# s3-pilot2.net
KiCad netlist of a schematic drawn in EAGLE
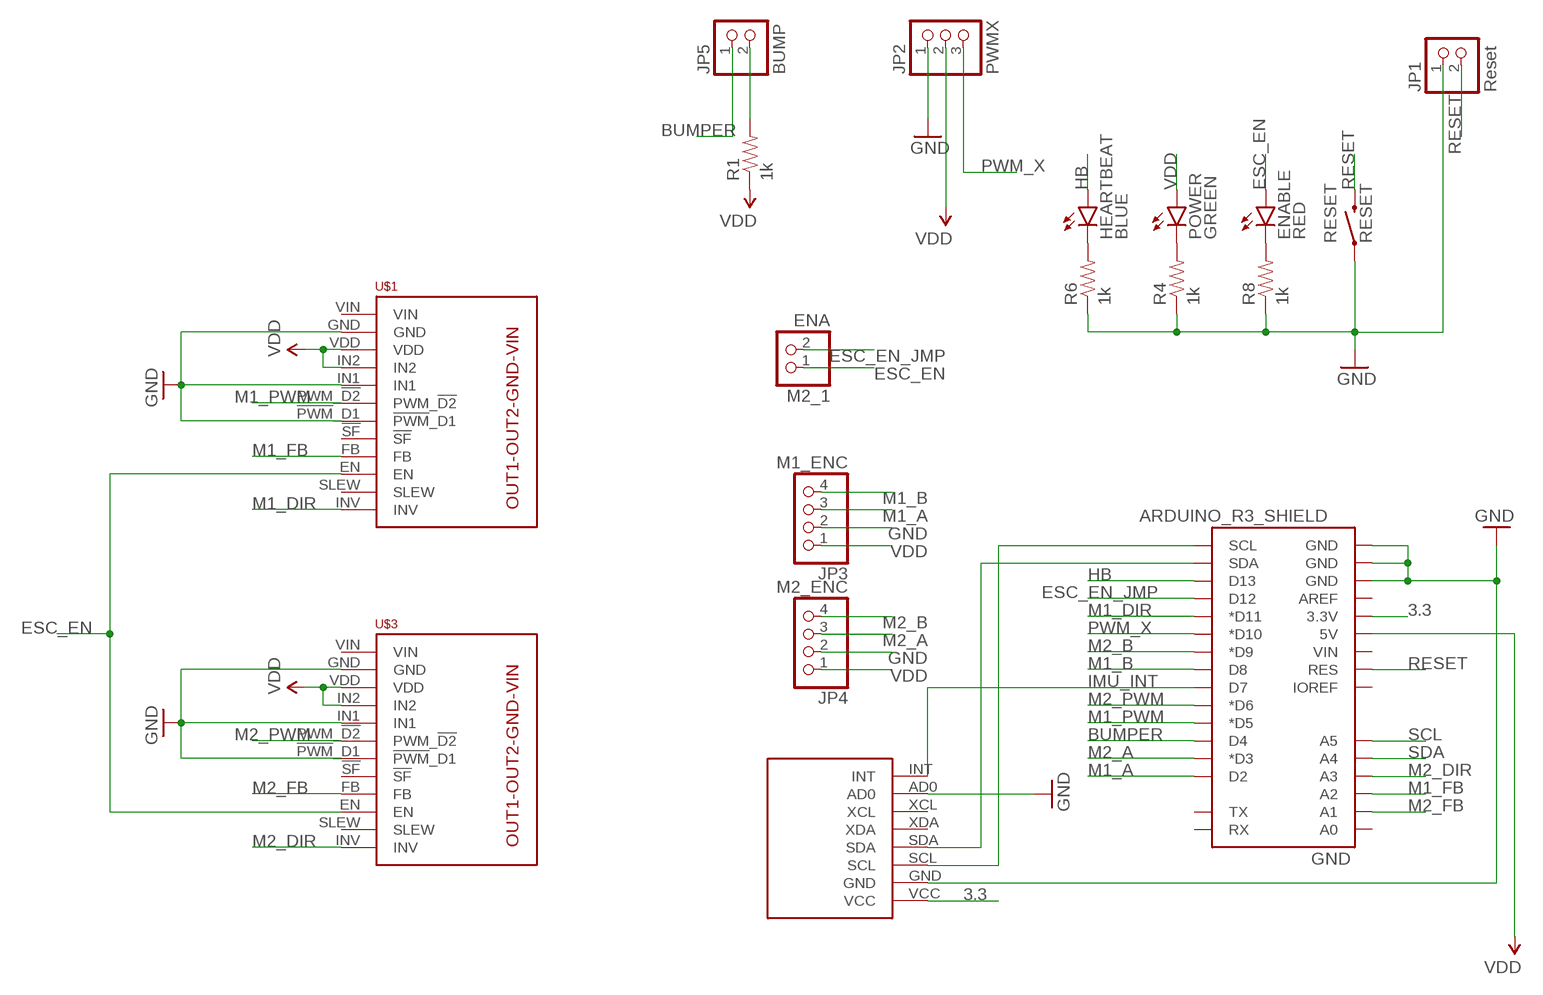
[diagram p0: schematic, sheet 1]

(export (version "E")
  (design (tool "Eeschema 10.0.6"))
  (components
    (comp (ref "ENABLE")
      (value "RED")
      (footprint "eagle-import:LED-1206")
      (libsource (lib "eagle-import") (part "LED-RED1206"))
    )
    (comp (ref "GND")
      (value "ARDUINO_R3_SHIELD")
      (footprint "eagle-import:UNO_R3_SHIELD")
      (libsource (lib "eagle-import") (part "ARDUINO_R3_SHIELD"))
    )
    (comp (ref "HEARTBEAT")
      (value "BLUE")
      (footprint "eagle-import:LED-1206")
      (libsource (lib "eagle-import") (part "LED-BLUE1206"))
    )
    (comp (ref "JP1")
      (value "Reset")
      (footprint "eagle-import:1X02")
      (libsource (lib "eagle-import") (part "PINHD-1X2"))
    )
    (comp (ref "JP2")
      (value "PWMX")
      (footprint "eagle-import:1X03_90")
      (libsource (lib "eagle-import") (part "PINHD-1X3/90"))
    )
    (comp (ref "JP3")
      (value "M1_ENC")
      (footprint "eagle-import:1X04_90")
      (libsource (lib "eagle-import") (part "PINHD-1X4/90"))
    )
    (comp (ref "JP4")
      (value "M2_ENC")
      (footprint "eagle-import:1X04_90")
      (libsource (lib "eagle-import") (part "PINHD-1X4/90"))
    )
    (comp (ref "JP5")
      (value "BUMP")
      (footprint "eagle-import:1X02_90")
      (libsource (lib "eagle-import") (part "PINHD-1X2/90"))
    )
    (comp (ref "M2_1")
      (value "ENA")
      (footprint "eagle-import:1X02")
      (libsource (lib "eagle-import") (part "PINHD-1X2"))
    )
    (comp (ref "MPU6050")
      (value "MPU-6050-BO")
      (footprint "eagle-import:MPU-6050-BO")
      (libsource (lib "eagle-import") (part "MPU-6050-BO"))
    )
    (comp (ref "POWER")
      (value "GREEN")
      (footprint "eagle-import:LED-1206")
      (libsource (lib "eagle-import") (part "LED-GREENLARGE"))
    )
    (comp (ref "R1")
      (value "1k")
      (footprint "eagle-import:1206")
      (libsource (lib "eagle-import") (part "RESISTOR1206"))
    )
    (comp (ref "R4")
      (value "1k")
      (footprint "eagle-import:1206")
      (libsource (lib "eagle-import") (part "RESISTOR1206"))
    )
    (comp (ref "R6")
      (value "1k")
      (footprint "eagle-import:1206")
      (libsource (lib "eagle-import") (part "RESISTOR1206"))
    )
    (comp (ref "R8")
      (value "1k")
      (footprint "eagle-import:1206")
      (libsource (lib "eagle-import") (part "RESISTOR1206"))
    )
    (comp (ref "RESET")
      (value "RESET")
      (footprint "eagle-import:TACTILE_SWITCH_TALL")
      (libsource (lib "eagle-import") (part "SWITCH-MOMENTARY-2SMD-4"))
    )
    (comp (ref "U$1")
      (value "M1")
      (footprint "eagle-import:MC33926-SINGLE-BO")
      (libsource (lib "eagle-import") (part "MC33926-SINGLE-BO"))
    )
    (comp (ref "U$3")
      (value "M2")
      (footprint "eagle-import:MC33926-SINGLE-BO")
      (libsource (lib "eagle-import") (part "MC33926-SINGLE-BO"))
    )
  )
  (nets
    (net (code "1") (name "/3.3") (class "Default")
      (node (ref "GND") (pin "3.3V") (pinfunction "3.3V_3.3V") (pintype "bidirectional"))
      (node (ref "MPU6050") (pin "VCC") (pinfunction "VCC_VCC") (pintype "power_in"))
    )
    (net (code "2") (name "/BUMPER") (class "Default")
      (node (ref "GND") (pin "D4") (pinfunction "D4_D4") (pintype "bidirectional"))
      (node (ref "JP5") (pin "1") (pinfunction "1_1") (pintype "passive"))
    )
    (net (code "3") (name "/ESC_EN") (class "Default")
      (node (ref "ENABLE") (pin "A") (pinfunction "A_A") (pintype "passive"))
      (node (ref "M2_1") (pin "1") (pinfunction "1_1") (pintype "passive"))
      (node (ref "U$1") (pin "EN") (pinfunction "EN_EN") (pintype "input"))
      (node (ref "U$3") (pin "EN") (pinfunction "EN_EN") (pintype "input"))
    )
    (net (code "4") (name "/ESC_EN_JMP") (class "Default")
      (node (ref "GND") (pin "D12") (pinfunction "D12_D12") (pintype "bidirectional"))
      (node (ref "M2_1") (pin "2") (pinfunction "2_2") (pintype "passive"))
    )
    (net (code "5") (name "/HB") (class "Default")
      (node (ref "GND") (pin "D13") (pinfunction "D13_D13") (pintype "bidirectional"))
      (node (ref "HEARTBEAT") (pin "A") (pinfunction "A_A") (pintype "passive"))
    )
    (net (code "6") (name "/IMU_INT") (class "Default")
      (node (ref "GND") (pin "D7") (pinfunction "D7_D7") (pintype "bidirectional"))
      (node (ref "MPU6050") (pin "INT") (pinfunction "INT_INT") (pintype "output"))
    )
    (net (code "7") (name "/M1_A") (class "Default")
      (node (ref "GND") (pin "D2") (pinfunction "D2_D2") (pintype "bidirectional"))
      (node (ref "JP3") (pin "3") (pinfunction "3_3") (pintype "passive"))
    )
    (net (code "8") (name "/M1_B") (class "Default")
      (node (ref "GND") (pin "D8") (pinfunction "D8_D8") (pintype "bidirectional"))
      (node (ref "JP3") (pin "4") (pinfunction "4_4") (pintype "passive"))
    )
    (net (code "9") (name "/M1_DIR") (class "Default")
      (node (ref "GND") (pin "D11") (pinfunction "*D11_D11") (pintype "bidirectional"))
      (node (ref "U$1") (pin "INV") (pinfunction "INV_INV") (pintype "input"))
    )
    (net (code "10") (name "/M1_FB") (class "Default")
      (node (ref "GND") (pin "A2") (pinfunction "A2_A2") (pintype "bidirectional"))
      (node (ref "U$1") (pin "FB") (pinfunction "FB_FB") (pintype "output"))
    )
    (net (code "11") (name "/M1_PWM") (class "Default")
      (node (ref "GND") (pin "D5") (pinfunction "*D5_D5") (pintype "bidirectional"))
      (node (ref "U$1") (pin "PWM_!D2") (pinfunction "PWM_~{D2}_PWM_!D2") (pintype "input"))
    )
    (net (code "12") (name "/M2_A") (class "Default")
      (node (ref "GND") (pin "D3") (pinfunction "*D3_D3") (pintype "bidirectional"))
      (node (ref "JP4") (pin "3") (pinfunction "3_3") (pintype "passive"))
    )
    (net (code "13") (name "/M2_B") (class "Default")
      (node (ref "GND") (pin "D9") (pinfunction "*D9_D9") (pintype "bidirectional"))
      (node (ref "JP4") (pin "4") (pinfunction "4_4") (pintype "passive"))
    )
    (net (code "14") (name "/M2_DIR") (class "Default")
      (node (ref "GND") (pin "A3") (pinfunction "A3_A3") (pintype "bidirectional"))
      (node (ref "U$3") (pin "INV") (pinfunction "INV_INV") (pintype "input"))
    )
    (net (code "15") (name "/M2_FB") (class "Default")
      (node (ref "GND") (pin "A1") (pinfunction "A1_A1") (pintype "bidirectional"))
      (node (ref "U$3") (pin "FB") (pinfunction "FB_FB") (pintype "output"))
    )
    (net (code "16") (name "/M2_PWM") (class "Default")
      (node (ref "GND") (pin "D6") (pinfunction "*D6_D6") (pintype "bidirectional"))
      (node (ref "U$3") (pin "PWM_!D2") (pinfunction "PWM_~{D2}_PWM_!D2") (pintype "input"))
    )
    (net (code "17") (name "/PWM_X") (class "Default")
      (node (ref "GND") (pin "D10") (pinfunction "*D10_D10") (pintype "bidirectional"))
      (node (ref "JP2") (pin "3") (pinfunction "3_3") (pintype "passive"))
    )
    (net (code "18") (name "/RESET") (class "Default")
      (node (ref "GND") (pin "RES") (pinfunction "RES_RES") (pintype "bidirectional"))
      (node (ref "JP1") (pin "2") (pinfunction "2_2") (pintype "passive"))
      (node (ref "RESET") (pin "B2") (pinfunction "2_B2") (pintype "passive"))
    )
    (net (code "19") (name "/SCL") (class "Default")
      (node (ref "GND") (pin "A5") (pinfunction "A5_A5") (pintype "bidirectional"))
      (node (ref "GND") (pin "SCL") (pinfunction "SCL_SCL") (pintype "bidirectional"))
      (node (ref "MPU6050") (pin "SCL") (pinfunction "SCL_SCL") (pintype "bidirectional"))
    )
    (net (code "20") (name "/SDA") (class "Default")
      (node (ref "GND") (pin "A4") (pinfunction "A4_A4") (pintype "bidirectional"))
      (node (ref "GND") (pin "SDA") (pinfunction "SDA_SDA") (pintype "bidirectional"))
      (node (ref "MPU6050") (pin "SDA") (pinfunction "SDA_SDA") (pintype "bidirectional"))
    )
    (net (code "21") (name "GND") (class "Default")
      (node (ref "GND") (pin "GND@0") (pinfunction "GND_GND@0") (pintype "bidirectional"))
      (node (ref "GND") (pin "GND@1") (pinfunction "GND_GND@1") (pintype "bidirectional"))
      (node (ref "GND") (pin "GND@2") (pinfunction "GND_GND@2") (pintype "bidirectional"))
      (node (ref "JP1") (pin "1") (pinfunction "1_1") (pintype "passive"))
      (node (ref "JP2") (pin "1") (pinfunction "1_1") (pintype "passive"))
      (node (ref "JP3") (pin "2") (pinfunction "2_2") (pintype "passive"))
      (node (ref "JP4") (pin "2") (pinfunction "2_2") (pintype "passive"))
      (node (ref "MPU6050") (pin "AD0") (pinfunction "AD0_AD0") (pintype "input"))
      (node (ref "MPU6050") (pin "GND") (pinfunction "GND_GND") (pintype "power_in"))
      (node (ref "R4") (pin "1") (pinfunction "1_1") (pintype "passive"))
      (node (ref "R6") (pin "1") (pinfunction "1_1") (pintype "passive"))
      (node (ref "R8") (pin "1") (pinfunction "1_1") (pintype "passive"))
      (node (ref "RESET") (pin "A2") (pinfunction "1_A2") (pintype "passive"))
      (node (ref "U$1") (pin "!PWM!_D1") (pinfunction "~{PWM}_D1_!PWM!_D1") (pintype "input"))
      (node (ref "U$1") (pin "GND") (pinfunction "GND_GND") (pintype "power_in"))
      (node (ref "U$1") (pin "IN1") (pinfunction "IN1_IN1") (pintype "input"))
      (node (ref "U$3") (pin "!PWM!_D1") (pinfunction "~{PWM}_D1_!PWM!_D1") (pintype "input"))
      (node (ref "U$3") (pin "GND") (pinfunction "GND_GND") (pintype "power_in"))
      (node (ref "U$3") (pin "IN1") (pinfunction "IN1_IN1") (pintype "input"))
    )
    (net (code "22") (name "Net-(ENABLE-PadC)") (class "Default")
      (node (ref "ENABLE") (pin "C") (pinfunction "C_C") (pintype "passive"))
      (node (ref "R8") (pin "2") (pinfunction "2_2") (pintype "passive"))
    )
    (net (code "23") (name "Net-(HEARTBEAT-PadC)") (class "Default")
      (node (ref "HEARTBEAT") (pin "C") (pinfunction "C_C") (pintype "passive"))
      (node (ref "R6") (pin "2") (pinfunction "2_2") (pintype "passive"))
    )
    (net (code "24") (name "Net-(JP5-Pad2)") (class "Default")
      (node (ref "JP5") (pin "2") (pinfunction "2_2") (pintype "passive"))
      (node (ref "R1") (pin "2") (pinfunction "2_2") (pintype "passive"))
    )
    (net (code "25") (name "Net-(POWER-PadC)") (class "Default")
      (node (ref "POWER") (pin "C") (pinfunction "C_C") (pintype "passive"))
      (node (ref "R4") (pin "2") (pinfunction "2_2") (pintype "passive"))
    )
    (net (code "26") (name "VDD") (class "Default")
      (node (ref "GND") (pin "5V") (pinfunction "5V_5V") (pintype "bidirectional"))
      (node (ref "JP2") (pin "2") (pinfunction "2_2") (pintype "passive"))
      (node (ref "JP3") (pin "1") (pinfunction "1_1") (pintype "passive"))
      (node (ref "JP4") (pin "1") (pinfunction "1_1") (pintype "passive"))
      (node (ref "POWER") (pin "A") (pinfunction "A_A") (pintype "passive"))
      (node (ref "R1") (pin "1") (pinfunction "1_1") (pintype "passive"))
      (node (ref "U$1") (pin "IN2") (pinfunction "IN2_IN2") (pintype "input"))
      (node (ref "U$1") (pin "VDD") (pinfunction "VDD_VDD") (pintype "power_in"))
      (node (ref "U$3") (pin "IN2") (pinfunction "IN2_IN2") (pintype "input"))
      (node (ref "U$3") (pin "VDD") (pinfunction "VDD_VDD") (pintype "power_in"))
    )
    (net (code "27") (name "unconnected-(GND-PadA0)") (class "Default")
      (node (ref "GND") (pin "A0") (pinfunction "A0_A0") (pintype "bidirectional"))
    )
    (net (code "28") (name "unconnected-(GND-PadAREF)") (class "Default")
      (node (ref "GND") (pin "AREF") (pinfunction "AREF_AREF") (pintype "bidirectional"))
    )
    (net (code "29") (name "unconnected-(GND-PadIOREF)") (class "Default")
      (node (ref "GND") (pin "IOREF") (pinfunction "IOREF_IOREF") (pintype "bidirectional"))
    )
    (net (code "30") (name "unconnected-(GND-PadRX)") (class "Default")
      (node (ref "GND") (pin "RX") (pinfunction "RX_RX") (pintype "bidirectional"))
    )
    (net (code "31") (name "unconnected-(GND-PadTX)") (class "Default")
      (node (ref "GND") (pin "TX") (pinfunction "TX_TX") (pintype "bidirectional"))
    )
    (net (code "32") (name "unconnected-(GND-PadVIN)") (class "Default")
      (node (ref "GND") (pin "VIN") (pinfunction "VIN_VIN") (pintype "bidirectional"))
    )
    (net (code "33") (name "unconnected-(MPU6050-PadXCL)") (class "Default")
      (node (ref "MPU6050") (pin "XCL") (pinfunction "XCL_XCL") (pintype "bidirectional"))
    )
    (net (code "34") (name "unconnected-(MPU6050-PadXDA)") (class "Default")
      (node (ref "MPU6050") (pin "XDA") (pinfunction "XDA_XDA") (pintype "bidirectional"))
    )
    (net (code "35") (name "unconnected-(U$1-PadSLEW)") (class "Default")
      (node (ref "U$1") (pin "SLEW") (pinfunction "SLEW_SLEW") (pintype "input"))
    )
    (net (code "36") (name "unconnected-(U$1-PadVIN)") (class "Default")
      (node (ref "U$1") (pin "VIN") (pinfunction "VIN_VIN") (pintype "no_connect"))
    )
    (net (code "37") (name "unconnected-(U$1-~{SF}-Pad!SF)") (class "Default")
      (node (ref "U$1") (pin "!SF") (pinfunction "~{SF}_!SF") (pintype "output"))
    )
    (net (code "38") (name "unconnected-(U$3-PadSLEW)") (class "Default")
      (node (ref "U$3") (pin "SLEW") (pinfunction "SLEW_SLEW") (pintype "input"))
    )
    (net (code "39") (name "unconnected-(U$3-PadVIN)") (class "Default")
      (node (ref "U$3") (pin "VIN") (pinfunction "VIN_VIN") (pintype "no_connect"))
    )
    (net (code "40") (name "unconnected-(U$3-~{SF}-Pad!SF)") (class "Default")
      (node (ref "U$3") (pin "!SF") (pinfunction "~{SF}_!SF") (pintype "output"))
    )
  )
)
